# 8_HDMI2.net
KiCad netlist of a schematic drawn in Altium Designer
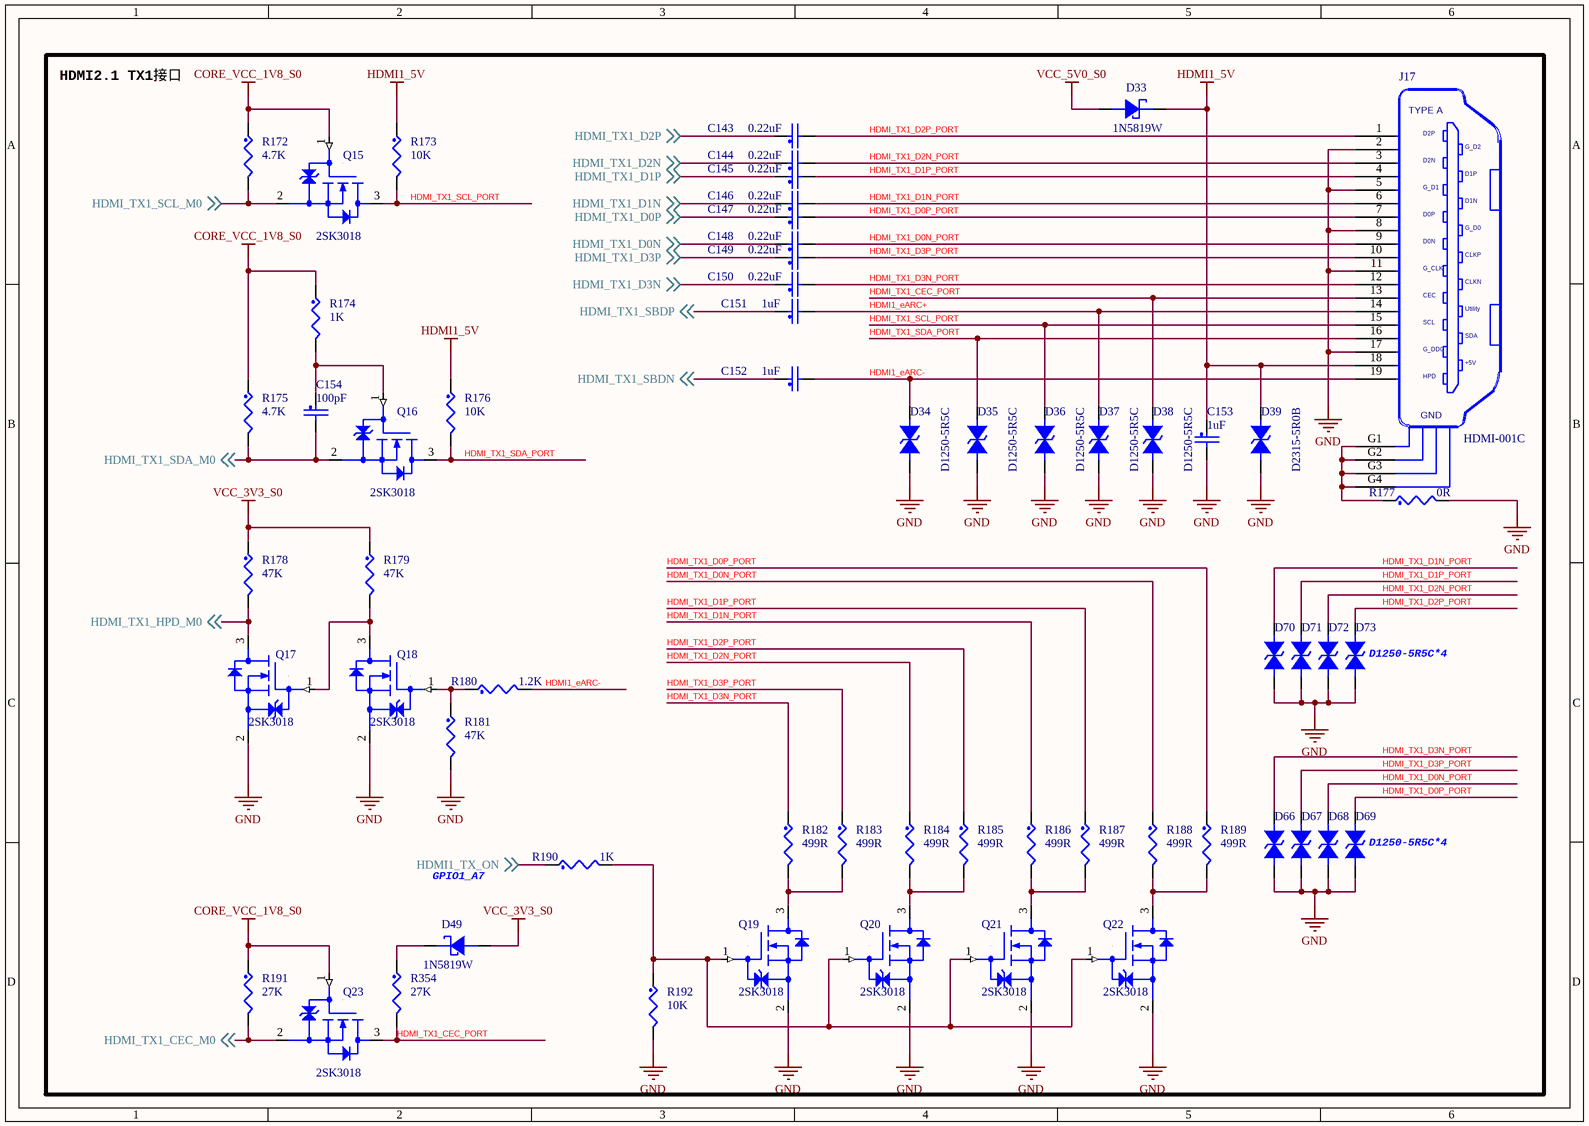
[diagram p0: 8.HDMI2.SchDoc]

(export (version "E")
  (design (tool "Eeschema 10.0.6"))
  (components
    (comp (ref "C143")
      (value "0.22uF")
      (footprint "0.PCB1:C0402")
      (libsource (lib "RK3588底板") (part "CAP_NP"))
    )
    (comp (ref "C144")
      (value "0.22uF")
      (footprint "0.PCB1:C0402")
      (libsource (lib "RK3588底板") (part "CAP_NP"))
    )
    (comp (ref "C145")
      (value "0.22uF")
      (footprint "0.PCB1:C0402")
      (libsource (lib "RK3588底板") (part "CAP_NP"))
    )
    (comp (ref "C146")
      (value "0.22uF")
      (footprint "0.PCB1:C0402")
      (libsource (lib "RK3588底板") (part "CAP_NP"))
    )
    (comp (ref "C147")
      (value "0.22uF")
      (footprint "0.PCB1:C0402")
      (libsource (lib "RK3588底板") (part "CAP_NP"))
    )
    (comp (ref "C148")
      (value "0.22uF")
      (footprint "0.PCB1:C0402")
      (libsource (lib "RK3588底板") (part "CAP_NP"))
    )
    (comp (ref "C149")
      (value "0.22uF")
      (footprint "0.PCB1:C0402")
      (libsource (lib "RK3588底板") (part "CAP_NP"))
    )
    (comp (ref "C150")
      (value "0.22uF")
      (footprint "0.PCB1:C0402")
      (libsource (lib "RK3588底板") (part "CAP_NP"))
    )
    (comp (ref "C151") (value "1uF") (footprint "0.PCB1:C0402") (libsource (lib "RK3588底板") (part "CAP_NP")))
    (comp (ref "C152") (value "1uF") (footprint "0.PCB1:C0402") (libsource (lib "RK3588底板") (part "CAP_NP")))
    (comp (ref "C153") (value "1uF") (footprint "0.PCB1:C0402") (libsource (lib "RK3588底板") (part "CAP_NP")))
    (comp (ref "C154")
      (value "100pF")
      (footprint "0.PCB1:C0402")
      (libsource (lib "RK3588底板") (part "CAP_NP"))
    )
    (comp (ref "D33")
      (value "1N5819W")
      (footprint "0.PCB1:SOD-123")
      (libsource (lib "RK3588底板") (part "DIODE_SCHTKY"))
    )
    (comp (ref "D34")
      (value "D1250-5R5C")
      (footprint "0.PCB1:esd0402")
      (libsource (lib "RK3588底板") (part "DIODE BI-DIR TRIG"))
    )
    (comp (ref "D35")
      (value "D1250-5R5C")
      (footprint "0.PCB1:esd0402")
      (libsource (lib "RK3588底板") (part "DIODE BI-DIR TRIG"))
    )
    (comp (ref "D36")
      (value "D1250-5R5C")
      (footprint "0.PCB1:esd0402")
      (libsource (lib "RK3588底板") (part "DIODE BI-DIR TRIG"))
    )
    (comp (ref "D37")
      (value "D1250-5R5C")
      (footprint "0.PCB1:esd0402")
      (libsource (lib "RK3588底板") (part "DIODE BI-DIR TRIG"))
    )
    (comp (ref "D38")
      (value "D1250-5R5C")
      (footprint "0.PCB1:esd0402")
      (libsource (lib "RK3588底板") (part "DIODE BI-DIR TRIG"))
    )
    (comp (ref "D39")
      (value "D2315-5R0B")
      (footprint "0.PCB1:esd0402")
      (libsource (lib "RK3588底板") (part "DIODE BI-DIR TRIG"))
    )
    (comp (ref "D49")
      (value "1N5819W")
      (footprint "0.PCB1:SOD-123")
      (libsource (lib "RK3588底板") (part "DIODE_SCHTKY"))
    )
    (comp (ref "D66")
      (value "D1250-5R5C")
      (footprint "0.PCB1:esd0402")
      (libsource (lib "RK3588底板") (part "DIODE BI-DIR TRIG"))
    )
    (comp (ref "D67")
      (value "D1250-5R5C")
      (footprint "0.PCB1:esd0402")
      (libsource (lib "RK3588底板") (part "DIODE BI-DIR TRIG"))
    )
    (comp (ref "D68")
      (value "D1250-5R5C")
      (footprint "0.PCB1:esd0402")
      (libsource (lib "RK3588底板") (part "DIODE BI-DIR TRIG"))
    )
    (comp (ref "D69")
      (value "D1250-5R5C")
      (footprint "0.PCB1:esd0402")
      (libsource (lib "RK3588底板") (part "DIODE BI-DIR TRIG"))
    )
    (comp (ref "D70")
      (value "D1250-5R5C")
      (footprint "0.PCB1:esd0402")
      (libsource (lib "RK3588底板") (part "DIODE BI-DIR TRIG"))
    )
    (comp (ref "D71")
      (value "D1250-5R5C")
      (footprint "0.PCB1:esd0402")
      (libsource (lib "RK3588底板") (part "DIODE BI-DIR TRIG"))
    )
    (comp (ref "D72")
      (value "D1250-5R5C")
      (footprint "0.PCB1:esd0402")
      (libsource (lib "RK3588底板") (part "DIODE BI-DIR TRIG"))
    )
    (comp (ref "D73")
      (value "D1250-5R5C")
      (footprint "0.PCB1:esd0402")
      (libsource (lib "RK3588底板") (part "DIODE BI-DIR TRIG"))
    )
    (comp (ref "J17")
      (value "HDMI-001C")
      (footprint "0.PCB1:HDMI-SMD")
      (libsource (lib "RK3588底板") (part "HDMI-001C"))
    )
    (comp (ref "Q15")
      (value "2SK3018")
      (footprint "0.PCB1:SOT23")
      (libsource (lib "RK3588底板") (part "2SK3018"))
    )
    (comp (ref "Q16")
      (value "2SK3018")
      (footprint "0.PCB1:SOT23")
      (libsource (lib "RK3588底板") (part "2SK3018"))
    )
    (comp (ref "Q17")
      (value "2SK3018")
      (footprint "0.PCB1:SOT23")
      (libsource (lib "RK3588底板") (part "2SK3018"))
    )
    (comp (ref "Q18")
      (value "2SK3018")
      (footprint "0.PCB1:SOT23")
      (libsource (lib "RK3588底板") (part "2SK3018"))
    )
    (comp (ref "Q19")
      (value "2SK3018")
      (footprint "0.PCB1:SOT23")
      (libsource (lib "RK3588底板") (part "2SK3018"))
    )
    (comp (ref "Q20")
      (value "2SK3018")
      (footprint "0.PCB1:SOT23")
      (libsource (lib "RK3588底板") (part "2SK3018"))
    )
    (comp (ref "Q21")
      (value "2SK3018")
      (footprint "0.PCB1:SOT23")
      (libsource (lib "RK3588底板") (part "2SK3018"))
    )
    (comp (ref "Q22")
      (value "2SK3018")
      (footprint "0.PCB1:SOT23")
      (libsource (lib "RK3588底板") (part "2SK3018"))
    )
    (comp (ref "Q23")
      (value "2SK3018")
      (footprint "0.PCB1:SOT23")
      (libsource (lib "RK3588底板") (part "2SK3018"))
    )
    (comp (ref "R172") (value "4.7K") (footprint "0.PCB1:R0402") (libsource (lib "RK3588底板") (part "RES")))
    (comp (ref "R173") (value "10K") (footprint "0.PCB1:R0402") (libsource (lib "RK3588底板") (part "RES")))
    (comp (ref "R174") (value "1K") (footprint "0.PCB1:R0402") (libsource (lib "RK3588底板") (part "RES")))
    (comp (ref "R175") (value "4.7K") (footprint "0.PCB1:R0402") (libsource (lib "RK3588底板") (part "RES")))
    (comp (ref "R176") (value "10K") (footprint "0.PCB1:R0402") (libsource (lib "RK3588底板") (part "RES")))
    (comp (ref "R177") (value "0R") (footprint "0.PCB1:R0402") (libsource (lib "RK3588底板") (part "RES")))
    (comp (ref "R178") (value "47K") (footprint "0.PCB1:R0402") (libsource (lib "RK3588底板") (part "RES")))
    (comp (ref "R179") (value "47K") (footprint "0.PCB1:R0402") (libsource (lib "RK3588底板") (part "RES")))
    (comp (ref "R180") (value "1.2K") (footprint "0.PCB1:R0402") (libsource (lib "RK3588底板") (part "RES")))
    (comp (ref "R181") (value "47K") (footprint "0.PCB1:R0402") (libsource (lib "RK3588底板") (part "RES")))
    (comp (ref "R182") (value "499R") (footprint "0.PCB1:R0402") (libsource (lib "RK3588底板") (part "RES")))
    (comp (ref "R183") (value "499R") (footprint "0.PCB1:R0402") (libsource (lib "RK3588底板") (part "RES")))
    (comp (ref "R184") (value "499R") (footprint "0.PCB1:R0402") (libsource (lib "RK3588底板") (part "RES")))
    (comp (ref "R185") (value "499R") (footprint "0.PCB1:R0402") (libsource (lib "RK3588底板") (part "RES")))
    (comp (ref "R186") (value "499R") (footprint "0.PCB1:R0402") (libsource (lib "RK3588底板") (part "RES")))
    (comp (ref "R187") (value "499R") (footprint "0.PCB1:R0402") (libsource (lib "RK3588底板") (part "RES")))
    (comp (ref "R188") (value "499R") (footprint "0.PCB1:R0402") (libsource (lib "RK3588底板") (part "RES")))
    (comp (ref "R189") (value "499R") (footprint "0.PCB1:R0402") (libsource (lib "RK3588底板") (part "RES")))
    (comp (ref "R190") (value "1K") (footprint "0.PCB1:R0402") (libsource (lib "RK3588底板") (part "RES")))
    (comp (ref "R191") (value "27K") (footprint "0.PCB1:R0402") (libsource (lib "RK3588底板") (part "RES")))
    (comp (ref "R192") (value "10K") (footprint "0.PCB1:R0402") (libsource (lib "RK3588底板") (part "RES")))
    (comp (ref "R354") (value "27K") (footprint "0.PCB1:R0402") (libsource (lib "RK3588底板") (part "RES")))
  )
  (nets
    (net (code "1") (name "/HDMI1_eARC+") (class "Default")
      (node (ref "C151") (pin "2") (pinfunction "2_2") (pintype "passive"))
      (node (ref "D37") (pin "2") (pinfunction "2_2") (pintype "passive"))
      (node (ref "J17") (pin "14") (pinfunction "14_14") (pintype "passive"))
    )
    (net (code "2") (name "/HDMI1_eARC-") (class "Default")
      (node (ref "C152") (pin "2") (pinfunction "2_2") (pintype "passive"))
      (node (ref "D34") (pin "2") (pinfunction "2_2") (pintype "passive"))
      (node (ref "J17") (pin "19") (pinfunction "19_19") (pintype "passive"))
      (node (ref "R180") (pin "2") (pinfunction "2_2") (pintype "passive"))
    )
    (net (code "3") (name "/HDMI_TX1_CEC_PORT") (class "Default")
      (node (ref "D38") (pin "2") (pinfunction "2_2") (pintype "passive"))
      (node (ref "J17") (pin "13") (pinfunction "13_13") (pintype "passive"))
      (node (ref "Q23") (pin "3") (pinfunction "DRAIN_3") (pintype "passive"))
      (node (ref "R354") (pin "2") (pinfunction "2_2") (pintype "passive"))
    )
    (net (code "4") (name "/HDMI_TX1_D0N_PORT") (class "Default")
      (node (ref "C148") (pin "2") (pinfunction "2_2") (pintype "passive"))
      (node (ref "D68") (pin "2") (pinfunction "2_2") (pintype "passive"))
      (node (ref "J17") (pin "9") (pinfunction "9_9") (pintype "passive"))
      (node (ref "R188") (pin "1") (pinfunction "1_1") (pintype "passive"))
    )
    (net (code "5") (name "/HDMI_TX1_D0P_PORT") (class "Default")
      (node (ref "C147") (pin "2") (pinfunction "2_2") (pintype "passive"))
      (node (ref "D69") (pin "2") (pinfunction "2_2") (pintype "passive"))
      (node (ref "J17") (pin "7") (pinfunction "7_7") (pintype "passive"))
      (node (ref "R189") (pin "1") (pinfunction "1_1") (pintype "passive"))
    )
    (net (code "6") (name "/HDMI_TX1_D1N_PORT") (class "Default")
      (node (ref "C146") (pin "2") (pinfunction "2_2") (pintype "passive"))
      (node (ref "D70") (pin "2") (pinfunction "2_2") (pintype "passive"))
      (node (ref "J17") (pin "6") (pinfunction "6_6") (pintype "passive"))
      (node (ref "R186") (pin "1") (pinfunction "1_1") (pintype "passive"))
    )
    (net (code "7") (name "/HDMI_TX1_D1P_PORT") (class "Default")
      (node (ref "C145") (pin "2") (pinfunction "2_2") (pintype "passive"))
      (node (ref "D71") (pin "2") (pinfunction "2_2") (pintype "passive"))
      (node (ref "J17") (pin "4") (pinfunction "4_4") (pintype "passive"))
      (node (ref "R187") (pin "1") (pinfunction "1_1") (pintype "passive"))
    )
    (net (code "8") (name "/HDMI_TX1_D2N_PORT") (class "Default")
      (node (ref "C144") (pin "2") (pinfunction "2_2") (pintype "passive"))
      (node (ref "D72") (pin "2") (pinfunction "2_2") (pintype "passive"))
      (node (ref "J17") (pin "3") (pinfunction "3_3") (pintype "passive"))
      (node (ref "R184") (pin "1") (pinfunction "1_1") (pintype "passive"))
    )
    (net (code "9") (name "/HDMI_TX1_D2P_PORT") (class "Default")
      (node (ref "C143") (pin "2") (pinfunction "2_2") (pintype "passive"))
      (node (ref "D73") (pin "2") (pinfunction "2_2") (pintype "passive"))
      (node (ref "J17") (pin "1") (pinfunction "1_1") (pintype "passive"))
      (node (ref "R185") (pin "1") (pinfunction "1_1") (pintype "passive"))
    )
    (net (code "10") (name "/HDMI_TX1_D3N_PORT") (class "Default")
      (node (ref "C150") (pin "2") (pinfunction "2_2") (pintype "passive"))
      (node (ref "D66") (pin "2") (pinfunction "2_2") (pintype "passive"))
      (node (ref "J17") (pin "12") (pinfunction "12_12") (pintype "passive"))
      (node (ref "R182") (pin "1") (pinfunction "1_1") (pintype "passive"))
    )
    (net (code "11") (name "/HDMI_TX1_D3P_PORT") (class "Default")
      (node (ref "C149") (pin "2") (pinfunction "2_2") (pintype "passive"))
      (node (ref "D67") (pin "2") (pinfunction "2_2") (pintype "passive"))
      (node (ref "J17") (pin "10") (pinfunction "10_10") (pintype "passive"))
      (node (ref "R183") (pin "1") (pinfunction "1_1") (pintype "passive"))
    )
    (net (code "12") (name "/HDMI_TX1_SCL_PORT") (class "Default")
      (node (ref "D36") (pin "2") (pinfunction "2_2") (pintype "passive"))
      (node (ref "J17") (pin "15") (pinfunction "15_15") (pintype "passive"))
      (node (ref "Q15") (pin "3") (pinfunction "DRAIN_3") (pintype "passive"))
      (node (ref "R173") (pin "2") (pinfunction "2_2") (pintype "passive"))
    )
    (net (code "13") (name "/HDMI_TX1_SDA_PORT") (class "Default")
      (node (ref "D35") (pin "2") (pinfunction "2_2") (pintype "passive"))
      (node (ref "J17") (pin "16") (pinfunction "16_16") (pintype "passive"))
      (node (ref "Q16") (pin "3") (pinfunction "DRAIN_3") (pintype "passive"))
      (node (ref "R176") (pin "2") (pinfunction "2_2") (pintype "passive"))
    )
    (net (code "14") (name "CORE_VCC_1V8_S0") (class "Default")
      (node (ref "Q15") (pin "1") (pinfunction "GATE_1") (pintype "input"))
      (node (ref "Q23") (pin "1") (pinfunction "GATE_1") (pintype "input"))
      (node (ref "R172") (pin "1") (pinfunction "1_1") (pintype "passive"))
      (node (ref "R174") (pin "1") (pinfunction "1_1") (pintype "passive"))
      (node (ref "R175") (pin "1") (pinfunction "1_1") (pintype "passive"))
      (node (ref "R191") (pin "1") (pinfunction "1_1") (pintype "passive"))
    )
    (net (code "15") (name "GND") (class "Default")
      (node (ref "C153") (pin "2") (pinfunction "2_2") (pintype "passive"))
      (node (ref "D34") (pin "1") (pinfunction "1_1") (pintype "passive"))
      (node (ref "D35") (pin "1") (pinfunction "1_1") (pintype "passive"))
      (node (ref "D36") (pin "1") (pinfunction "1_1") (pintype "passive"))
      (node (ref "D37") (pin "1") (pinfunction "1_1") (pintype "passive"))
      (node (ref "D38") (pin "1") (pinfunction "1_1") (pintype "passive"))
      (node (ref "D39") (pin "1") (pinfunction "1_1") (pintype "passive"))
      (node (ref "D66") (pin "1") (pinfunction "1_1") (pintype "passive"))
      (node (ref "D67") (pin "1") (pinfunction "1_1") (pintype "passive"))
      (node (ref "D68") (pin "1") (pinfunction "1_1") (pintype "passive"))
      (node (ref "D69") (pin "1") (pinfunction "1_1") (pintype "passive"))
      (node (ref "D70") (pin "1") (pinfunction "1_1") (pintype "passive"))
      (node (ref "D71") (pin "1") (pinfunction "1_1") (pintype "passive"))
      (node (ref "D72") (pin "1") (pinfunction "1_1") (pintype "passive"))
      (node (ref "D73") (pin "1") (pinfunction "1_1") (pintype "passive"))
      (node (ref "J17") (pin "11") (pinfunction "11_11") (pintype "passive"))
      (node (ref "J17") (pin "17") (pinfunction "17_17") (pintype "passive"))
      (node (ref "J17") (pin "2") (pinfunction "2_2") (pintype "passive"))
      (node (ref "J17") (pin "5") (pinfunction "5_5") (pintype "passive"))
      (node (ref "J17") (pin "8") (pinfunction "8_8") (pintype "passive"))
      (node (ref "Q17") (pin "2") (pinfunction "SOURCE_2") (pintype "passive"))
      (node (ref "Q18") (pin "2") (pinfunction "SOURCE_2") (pintype "passive"))
      (node (ref "Q19") (pin "2") (pinfunction "SOURCE_2") (pintype "passive"))
      (node (ref "Q20") (pin "2") (pinfunction "SOURCE_2") (pintype "passive"))
      (node (ref "Q21") (pin "2") (pinfunction "SOURCE_2") (pintype "passive"))
      (node (ref "Q22") (pin "2") (pinfunction "SOURCE_2") (pintype "passive"))
      (node (ref "R177") (pin "2") (pinfunction "2_2") (pintype "passive"))
      (node (ref "R181") (pin "2") (pinfunction "2_2") (pintype "passive"))
      (node (ref "R192") (pin "2") (pinfunction "2_2") (pintype "passive"))
    )
    (net (code "16") (name "HDMI1_5V") (class "Default")
      (node (ref "C153") (pin "1") (pinfunction "1_1") (pintype "passive"))
      (node (ref "D33") (pin "1") (pinfunction "1_1") (pintype "passive"))
      (node (ref "D39") (pin "2") (pinfunction "2_2") (pintype "passive"))
      (node (ref "J17") (pin "18") (pinfunction "18_18") (pintype "passive"))
      (node (ref "R173") (pin "1") (pinfunction "1_1") (pintype "passive"))
      (node (ref "R176") (pin "1") (pinfunction "1_1") (pintype "passive"))
    )
    (net (code "17") (name "HDMI1_TX_ON") (class "Default")
      (node (ref "R190") (pin "1") (pinfunction "1_1") (pintype "passive"))
    )
    (net (code "18") (name "HDMI_TX1_CEC_M0") (class "Default")
      (node (ref "Q23") (pin "2") (pinfunction "SOURCE_2") (pintype "passive"))
      (node (ref "R191") (pin "2") (pinfunction "2_2") (pintype "passive"))
    )
    (net (code "19") (name "HDMI_TX1_D0N") (class "Default")
      (node (ref "C148") (pin "1") (pinfunction "1_1") (pintype "passive"))
    )
    (net (code "20") (name "HDMI_TX1_D0P") (class "Default")
      (node (ref "C147") (pin "1") (pinfunction "1_1") (pintype "passive"))
    )
    (net (code "21") (name "HDMI_TX1_D1N") (class "Default")
      (node (ref "C146") (pin "1") (pinfunction "1_1") (pintype "passive"))
    )
    (net (code "22") (name "HDMI_TX1_D1P") (class "Default")
      (node (ref "C145") (pin "1") (pinfunction "1_1") (pintype "passive"))
    )
    (net (code "23") (name "HDMI_TX1_D2N") (class "Default")
      (node (ref "C144") (pin "1") (pinfunction "1_1") (pintype "passive"))
    )
    (net (code "24") (name "HDMI_TX1_D2P") (class "Default")
      (node (ref "C143") (pin "1") (pinfunction "1_1") (pintype "passive"))
    )
    (net (code "25") (name "HDMI_TX1_D3N") (class "Default")
      (node (ref "C150") (pin "1") (pinfunction "1_1") (pintype "passive"))
    )
    (net (code "26") (name "HDMI_TX1_D3P") (class "Default")
      (node (ref "C149") (pin "1") (pinfunction "1_1") (pintype "passive"))
    )
    (net (code "27") (name "HDMI_TX1_HPD_M0") (class "Default")
      (node (ref "Q17") (pin "3") (pinfunction "DRAIN_3") (pintype "passive"))
      (node (ref "R178") (pin "2") (pinfunction "2_2") (pintype "passive"))
    )
    (net (code "28") (name "HDMI_TX1_SBDN") (class "Default")
      (node (ref "C152") (pin "1") (pinfunction "1_1") (pintype "passive"))
    )
    (net (code "29") (name "HDMI_TX1_SBDP") (class "Default")
      (node (ref "C151") (pin "1") (pinfunction "1_1") (pintype "passive"))
    )
    (net (code "30") (name "HDMI_TX1_SCL_M0") (class "Default")
      (node (ref "Q15") (pin "2") (pinfunction "SOURCE_2") (pintype "passive"))
      (node (ref "R172") (pin "2") (pinfunction "2_2") (pintype "passive"))
    )
    (net (code "31") (name "HDMI_TX1_SDA_M0") (class "Default")
      (node (ref "C154") (pin "2") (pinfunction "2_2") (pintype "passive"))
      (node (ref "Q16") (pin "2") (pinfunction "SOURCE_2") (pintype "passive"))
      (node (ref "R175") (pin "2") (pinfunction "2_2") (pintype "passive"))
    )
    (net (code "32") (name "Net-(D49-Pad1)") (class "Default")
      (node (ref "D49") (pin "1") (pinfunction "1_1") (pintype "passive"))
      (node (ref "R354") (pin "1") (pinfunction "1_1") (pintype "passive"))
    )
    (net (code "33") (name "Net-(J17-20)") (class "Default")
      (node (ref "J17") (pin "G1") (pinfunction "20_G1") (pintype "passive"))
      (node (ref "J17") (pin "G2") (pinfunction "21_G2") (pintype "passive"))
      (node (ref "J17") (pin "G3") (pinfunction "22_G3") (pintype "passive"))
      (node (ref "J17") (pin "G4") (pinfunction "23_G4") (pintype "passive"))
      (node (ref "R177") (pin "1") (pinfunction "1_1") (pintype "passive"))
    )
    (net (code "34") (name "Net-(Q16-GATE)") (class "Default")
      (node (ref "C154") (pin "1") (pinfunction "1_1") (pintype "passive"))
      (node (ref "Q16") (pin "1") (pinfunction "GATE_1") (pintype "input"))
      (node (ref "R174") (pin "2") (pinfunction "2_2") (pintype "passive"))
    )
    (net (code "35") (name "Net-(Q17-GATE)") (class "Default")
      (node (ref "Q17") (pin "1") (pinfunction "GATE_1") (pintype "input"))
      (node (ref "Q18") (pin "3") (pinfunction "DRAIN_3") (pintype "passive"))
      (node (ref "R179") (pin "2") (pinfunction "2_2") (pintype "passive"))
    )
    (net (code "36") (name "Net-(Q18-GATE)") (class "Default")
      (node (ref "Q18") (pin "1") (pinfunction "GATE_1") (pintype "input"))
      (node (ref "R180") (pin "1") (pinfunction "1_1") (pintype "passive"))
      (node (ref "R181") (pin "1") (pinfunction "1_1") (pintype "passive"))
    )
    (net (code "37") (name "Net-(Q19-DRAIN)") (class "Default")
      (node (ref "Q19") (pin "3") (pinfunction "DRAIN_3") (pintype "passive"))
      (node (ref "R182") (pin "2") (pinfunction "2_2") (pintype "passive"))
      (node (ref "R183") (pin "2") (pinfunction "2_2") (pintype "passive"))
    )
    (net (code "38") (name "Net-(Q19-GATE)") (class "Default")
      (node (ref "Q19") (pin "1") (pinfunction "GATE_1") (pintype "input"))
      (node (ref "Q20") (pin "1") (pinfunction "GATE_1") (pintype "input"))
      (node (ref "Q21") (pin "1") (pinfunction "GATE_1") (pintype "input"))
      (node (ref "Q22") (pin "1") (pinfunction "GATE_1") (pintype "input"))
      (node (ref "R190") (pin "2") (pinfunction "2_2") (pintype "passive"))
      (node (ref "R192") (pin "1") (pinfunction "1_1") (pintype "passive"))
    )
    (net (code "39") (name "Net-(Q20-DRAIN)") (class "Default")
      (node (ref "Q20") (pin "3") (pinfunction "DRAIN_3") (pintype "passive"))
      (node (ref "R184") (pin "2") (pinfunction "2_2") (pintype "passive"))
      (node (ref "R185") (pin "2") (pinfunction "2_2") (pintype "passive"))
    )
    (net (code "40") (name "Net-(Q21-DRAIN)") (class "Default")
      (node (ref "Q21") (pin "3") (pinfunction "DRAIN_3") (pintype "passive"))
      (node (ref "R186") (pin "2") (pinfunction "2_2") (pintype "passive"))
      (node (ref "R187") (pin "2") (pinfunction "2_2") (pintype "passive"))
    )
    (net (code "41") (name "Net-(Q22-DRAIN)") (class "Default")
      (node (ref "Q22") (pin "3") (pinfunction "DRAIN_3") (pintype "passive"))
      (node (ref "R188") (pin "2") (pinfunction "2_2") (pintype "passive"))
      (node (ref "R189") (pin "2") (pinfunction "2_2") (pintype "passive"))
    )
    (net (code "42") (name "VCC_3V3_S0") (class "Default")
      (node (ref "D49") (pin "2") (pinfunction "2_2") (pintype "passive"))
      (node (ref "R178") (pin "1") (pinfunction "1_1") (pintype "passive"))
      (node (ref "R179") (pin "1") (pinfunction "1_1") (pintype "passive"))
    )
    (net (code "43") (name "VCC_5V0_S0") (class "Default")
      (node (ref "D33") (pin "2") (pinfunction "2_2") (pintype "passive"))
    )
  )
)
